# I2C_Lego_PowerFunctions_Board_v1_0B.net
KiCad netlist of a schematic drawn in EAGLE
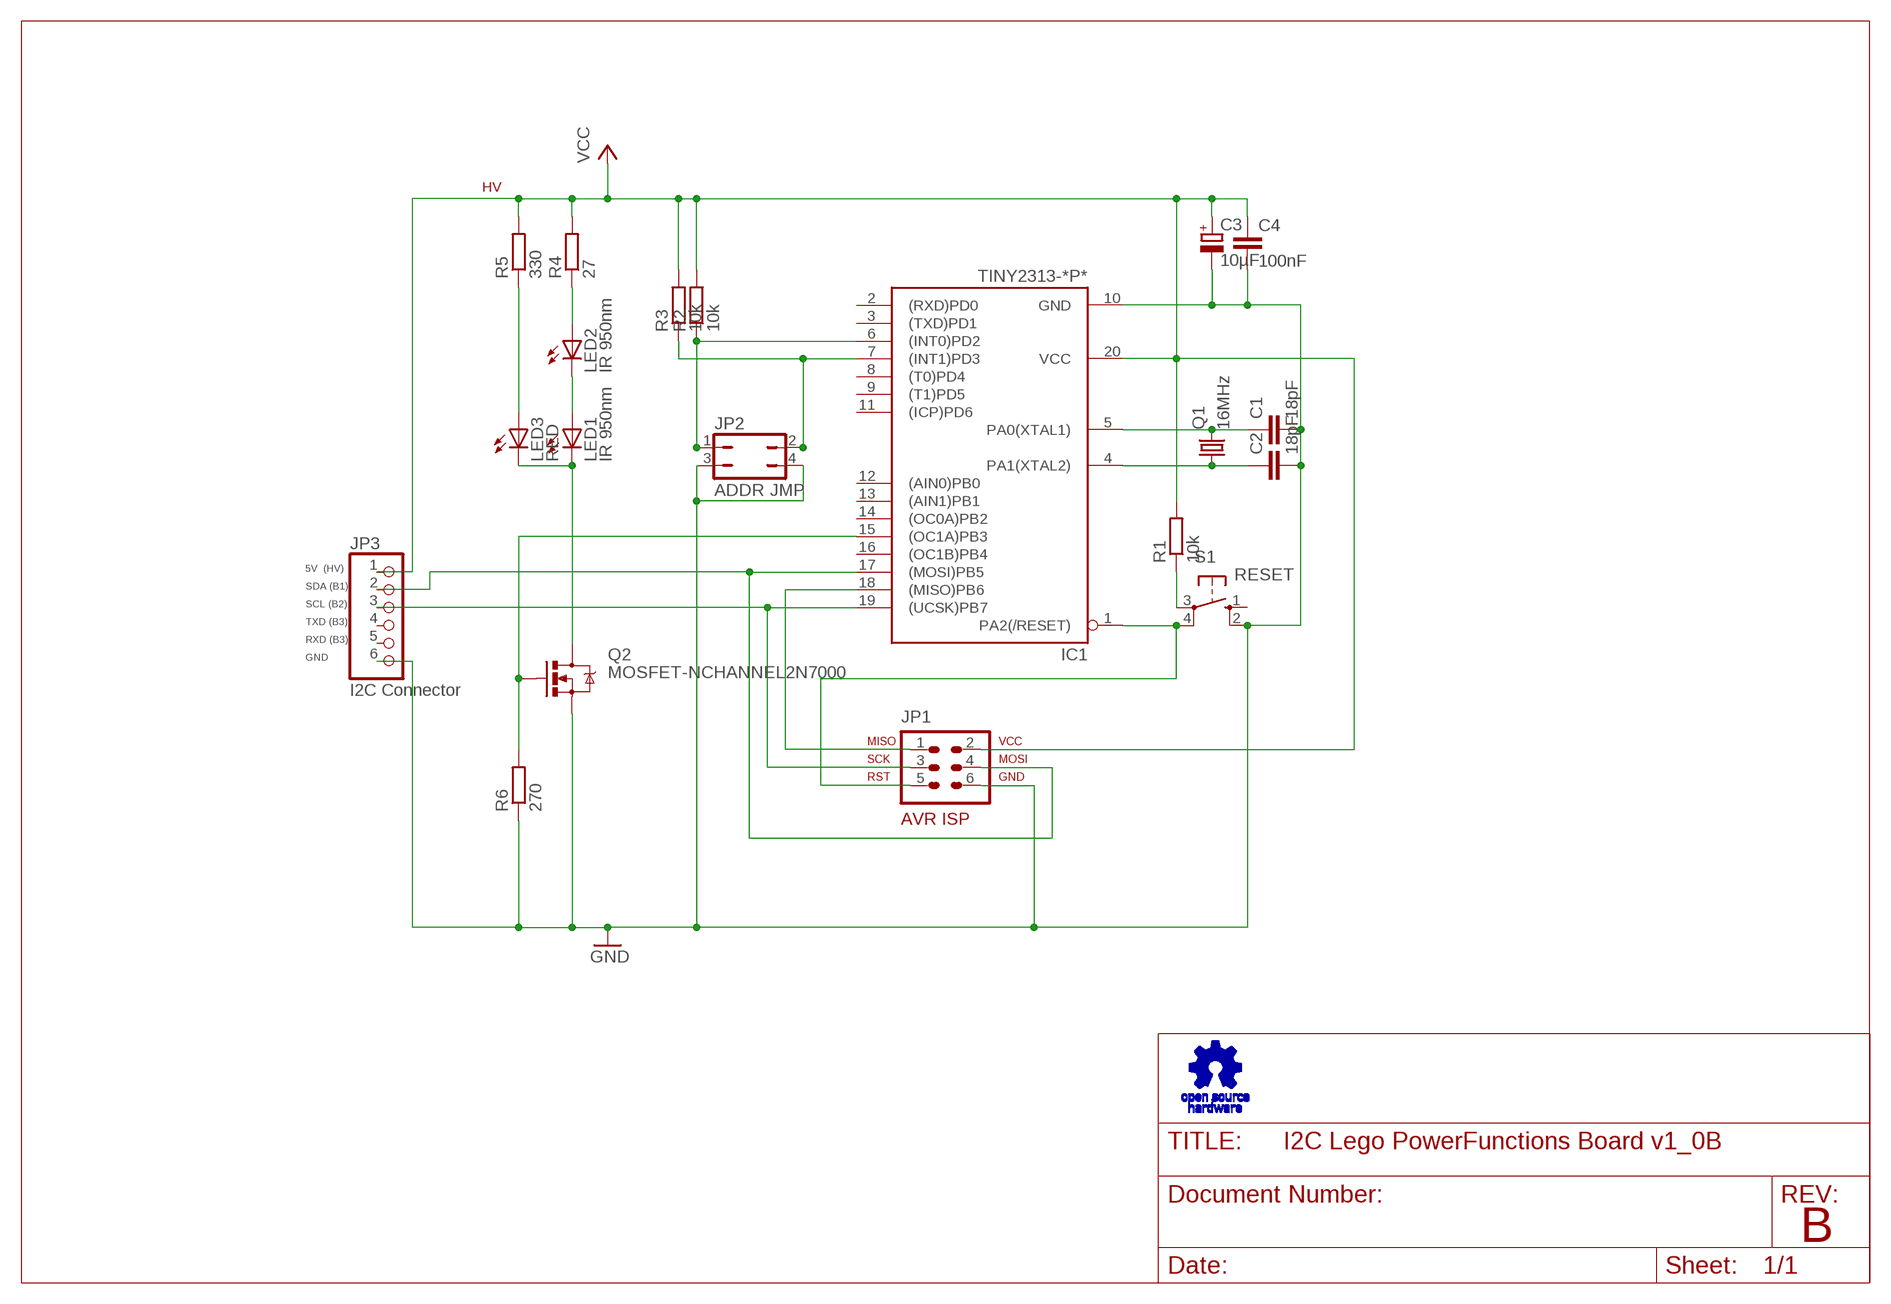
[diagram p0: schematic, sheet 1]

(export (version "E")
  (design (tool "Eeschema 10.0.6"))
  (components
    (comp (ref "C1")
      (value "18pF")
      (footprint "eagle-import:C025-025X050")
      (libsource (lib "eagle-import") (part "C-EU025-025X050"))
    )
    (comp (ref "C2")
      (value "18pF")
      (footprint "eagle-import:C025-025X050")
      (libsource (lib "eagle-import") (part "C-EU025-025X050"))
    )
    (comp (ref "C3")
      (value "10µF")
      (footprint "eagle-import:E2,5-6")
      (libsource (lib "eagle-import") (part "CPOL-EUE2.5-6"))
    )
    (comp (ref "C4")
      (value "100nF")
      (footprint "eagle-import:C050-030X075")
      (libsource (lib "eagle-import") (part "C-EU050-030X075"))
    )
    (comp (ref "IC1")
      (value "TINY2313-*P*")
      (footprint "eagle-import:DIL20")
      (libsource (lib "eagle-import") (part "TINY2313-P"))
    )
    (comp (ref "JP1")
      (value "AVR-ISP-6VERT")
      (footprint "eagle-import:AVR-ISP-6")
      (libsource (lib "eagle-import") (part "AVR-ISP-6VERT"))
    )
    (comp (ref "JP2")
      (value "ADDR JMP")
      (footprint "eagle-import:JP2Q")
      (libsource (lib "eagle-import") (part "JP2Q"))
    )
    (comp (ref "JP3")
      (value "I2C Connector")
      (footprint "eagle-import:1X06")
      (libsource (lib "eagle-import") (part "PINHD-1X6"))
    )
    (comp (ref "LED1")
      (value "IR 950nm")
      (footprint "eagle-import:LED5MM")
      (libsource (lib "eagle-import") (part "LED5MM"))
    )
    (comp (ref "LED2")
      (value "IR 950nm")
      (footprint "eagle-import:LED5MM")
      (libsource (lib "eagle-import") (part "LED5MM"))
    )
    (comp (ref "LED3")
      (value "RED")
      (footprint "eagle-import:LED3MM")
      (libsource (lib "eagle-import") (part "LED3MM"))
    )
    (comp (ref "Q1")
      (value "16MHz")
      (footprint "eagle-import:HC49_S")
      (libsource (lib "eagle-import") (part "CRYSTALHC49S"))
    )
    (comp (ref "Q2")
      (value "MOSFET-NCHANNEL2N7000")
      (footprint "eagle-import:TO-92")
      (libsource (lib "eagle-import") (part "MOSFET-NCHANNEL2N7000"))
    )
    (comp (ref "R1")
      (value "10k")
      (footprint "eagle-import:0207_10")
      (libsource (lib "eagle-import") (part "R-EU_0207_10"))
    )
    (comp (ref "R2")
      (value "10k")
      (footprint "eagle-import:0207_10")
      (libsource (lib "eagle-import") (part "R-EU_0207_10"))
    )
    (comp (ref "R3")
      (value "10k")
      (footprint "eagle-import:0207_10")
      (libsource (lib "eagle-import") (part "R-EU_0207_10"))
    )
    (comp (ref "R4")
      (value "27")
      (footprint "eagle-import:0207_10")
      (libsource (lib "eagle-import") (part "R-EU_0207_10"))
    )
    (comp (ref "R5")
      (value "330")
      (footprint "eagle-import:0207_10")
      (libsource (lib "eagle-import") (part "R-EU_0207_10"))
    )
    (comp (ref "R6")
      (value "270")
      (footprint "eagle-import:0207_10")
      (libsource (lib "eagle-import") (part "R-EU_0207_10"))
    )
    (comp (ref "S1")
      (value "RESET")
      (footprint "eagle-import:B3F-10XX")
      (fields (field (name "MPN") "B3F-1000"))
      (libsource (lib "eagle-import") (part "10-XX"))
    )
  )
  (nets
    (net (code "1") (name "GND") (class "Default")
      (node (ref "C1") (pin "2") (pinfunction "2_2") (pintype "passive"))
      (node (ref "C2") (pin "2") (pinfunction "2_2") (pintype "passive"))
      (node (ref "C3") (pin "-") (pinfunction "-_-") (pintype "passive"))
      (node (ref "C4") (pin "2") (pinfunction "2_2") (pintype "passive"))
      (node (ref "IC1") (pin "10") (pinfunction "GND_10") (pintype "power_in"))
      (node (ref "JP1") (pin "6") (pinfunction "6_6") (pintype "passive"))
      (node (ref "JP2") (pin "3") (pinfunction "3_3") (pintype "passive"))
      (node (ref "JP2") (pin "4") (pinfunction "4_4") (pintype "passive"))
      (node (ref "JP3") (pin "6") (pinfunction "6_6") (pintype "passive"))
      (node (ref "Q2") (pin "1") (pinfunction "S_1") (pintype "passive"))
      (node (ref "R6") (pin "1") (pinfunction "1_1") (pintype "passive"))
      (node (ref "S1") (pin "2") (pinfunction "S1_2") (pintype "passive"))
    )
    (net (code "2") (name "Net-(IC1-(INT0)PD2)") (class "Default")
      (node (ref "IC1") (pin "6") (pinfunction "(INT0)PD2_6") (pintype "bidirectional"))
      (node (ref "JP2") (pin "1") (pinfunction "1_1") (pintype "passive"))
      (node (ref "R2") (pin "1") (pinfunction "1_1") (pintype "passive"))
    )
    (net (code "3") (name "Net-(IC1-(INT1)PD3)") (class "Default")
      (node (ref "IC1") (pin "7") (pinfunction "(INT1)PD3_7") (pintype "bidirectional"))
      (node (ref "JP2") (pin "2") (pinfunction "2_2") (pintype "passive"))
      (node (ref "R3") (pin "1") (pinfunction "1_1") (pintype "passive"))
    )
    (net (code "4") (name "Net-(IC1-(MISO)PB6)") (class "Default")
      (node (ref "IC1") (pin "18") (pinfunction "(MISO)PB6_18") (pintype "bidirectional"))
      (node (ref "JP1") (pin "1") (pinfunction "1_1") (pintype "passive"))
    )
    (net (code "5") (name "Net-(IC1-(MOSI)PB5)") (class "Default")
      (node (ref "IC1") (pin "17") (pinfunction "(MOSI)PB5_17") (pintype "bidirectional"))
      (node (ref "JP1") (pin "4") (pinfunction "4_4") (pintype "passive"))
      (node (ref "JP3") (pin "2") (pinfunction "2_2") (pintype "passive"))
    )
    (net (code "6") (name "Net-(IC1-(OC1A)PB3)") (class "Default")
      (node (ref "IC1") (pin "15") (pinfunction "(OC1A)PB3_15") (pintype "bidirectional"))
      (node (ref "Q2") (pin "2") (pinfunction "G_2") (pintype "passive"))
      (node (ref "R6") (pin "2") (pinfunction "2_2") (pintype "passive"))
    )
    (net (code "7") (name "Net-(IC1-(UCSK)PB7)") (class "Default")
      (node (ref "IC1") (pin "19") (pinfunction "(UCSK)PB7_19") (pintype "bidirectional"))
      (node (ref "JP1") (pin "3") (pinfunction "3_3") (pintype "passive"))
      (node (ref "JP3") (pin "3") (pinfunction "3_3") (pintype "passive"))
    )
    (net (code "8") (name "Net-(IC1-PA0(XTAL1))") (class "Default")
      (node (ref "C1") (pin "1") (pinfunction "1_1") (pintype "passive"))
      (node (ref "IC1") (pin "5") (pinfunction "PA0(XTAL1)_5") (pintype "bidirectional"))
      (node (ref "Q1") (pin "2") (pinfunction "2_2") (pintype "passive"))
    )
    (net (code "9") (name "Net-(IC1-PA1(XTAL2))") (class "Default")
      (node (ref "C2") (pin "1") (pinfunction "1_1") (pintype "passive"))
      (node (ref "IC1") (pin "4") (pinfunction "PA1(XTAL2)_4") (pintype "bidirectional"))
      (node (ref "Q1") (pin "1") (pinfunction "1_1") (pintype "passive"))
    )
    (net (code "10") (name "Net-(IC1-PA2({slash}RESET))") (class "Default")
      (node (ref "IC1") (pin "1") (pinfunction "PA2(/RESET)_1") (pintype "input"))
      (node (ref "JP1") (pin "5") (pinfunction "5_5") (pintype "passive"))
      (node (ref "S1") (pin "4") (pinfunction "P1_4") (pintype "passive"))
    )
    (net (code "11") (name "Net-(LED1-C)") (class "Default")
      (node (ref "LED1") (pin "K") (pinfunction "C_K") (pintype "passive"))
      (node (ref "LED3") (pin "K") (pinfunction "C_K") (pintype "passive"))
      (node (ref "Q2") (pin "3") (pinfunction "D_3") (pintype "passive"))
    )
    (net (code "12") (name "Net-(LED2-C)") (class "Default")
      (node (ref "LED1") (pin "A") (pinfunction "A_A") (pintype "passive"))
      (node (ref "LED2") (pin "K") (pinfunction "C_K") (pintype "passive"))
    )
    (net (code "13") (name "Net-(LED2-PadA)") (class "Default")
      (node (ref "LED2") (pin "A") (pinfunction "A_A") (pintype "passive"))
      (node (ref "R4") (pin "1") (pinfunction "1_1") (pintype "passive"))
    )
    (net (code "14") (name "Net-(LED3-PadA)") (class "Default")
      (node (ref "LED3") (pin "A") (pinfunction "A_A") (pintype "passive"))
      (node (ref "R5") (pin "1") (pinfunction "1_1") (pintype "passive"))
    )
    (net (code "15") (name "Net-(S1-P)") (class "Default")
      (node (ref "R1") (pin "1") (pinfunction "1_1") (pintype "passive"))
      (node (ref "S1") (pin "3") (pinfunction "P_3") (pintype "passive"))
    )
    (net (code "16") (name "VCC") (class "Default")
      (node (ref "C3") (pin "+") (pinfunction "+_+") (pintype "passive"))
      (node (ref "C4") (pin "1") (pinfunction "1_1") (pintype "passive"))
      (node (ref "IC1") (pin "20") (pinfunction "VCC_20") (pintype "power_in"))
      (node (ref "JP1") (pin "2") (pinfunction "2_2") (pintype "passive"))
      (node (ref "JP3") (pin "1") (pinfunction "1_1") (pintype "passive"))
      (node (ref "R1") (pin "2") (pinfunction "2_2") (pintype "passive"))
      (node (ref "R2") (pin "2") (pinfunction "2_2") (pintype "passive"))
      (node (ref "R3") (pin "2") (pinfunction "2_2") (pintype "passive"))
      (node (ref "R4") (pin "2") (pinfunction "2_2") (pintype "passive"))
      (node (ref "R5") (pin "2") (pinfunction "2_2") (pintype "passive"))
    )
    (net (code "17") (name "unconnected-(IC1-(AIN0)PB0-Pad12)") (class "Default")
      (node (ref "IC1") (pin "12") (pinfunction "(AIN0)PB0_12") (pintype "bidirectional"))
    )
    (net (code "18") (name "unconnected-(IC1-(AIN1)PB1-Pad13)") (class "Default")
      (node (ref "IC1") (pin "13") (pinfunction "(AIN1)PB1_13") (pintype "bidirectional"))
    )
    (net (code "19") (name "unconnected-(IC1-(ICP)PD6-Pad11)") (class "Default")
      (node (ref "IC1") (pin "11") (pinfunction "(ICP)PD6_11") (pintype "bidirectional"))
    )
    (net (code "20") (name "unconnected-(IC1-(OC0A)PB2-Pad14)") (class "Default")
      (node (ref "IC1") (pin "14") (pinfunction "(OC0A)PB2_14") (pintype "bidirectional"))
    )
    (net (code "21") (name "unconnected-(IC1-(OC1B)PB4-Pad16)") (class "Default")
      (node (ref "IC1") (pin "16") (pinfunction "(OC1B)PB4_16") (pintype "bidirectional"))
    )
    (net (code "22") (name "unconnected-(IC1-(RXD)PD0-Pad2)") (class "Default")
      (node (ref "IC1") (pin "2") (pinfunction "(RXD)PD0_2") (pintype "bidirectional"))
    )
    (net (code "23") (name "unconnected-(IC1-(T0)PD4-Pad8)") (class "Default")
      (node (ref "IC1") (pin "8") (pinfunction "(T0)PD4_8") (pintype "bidirectional"))
    )
    (net (code "24") (name "unconnected-(IC1-(T1)PD5-Pad9)") (class "Default")
      (node (ref "IC1") (pin "9") (pinfunction "(T1)PD5_9") (pintype "bidirectional"))
    )
    (net (code "25") (name "unconnected-(IC1-(TXD)PD1-Pad3)") (class "Default")
      (node (ref "IC1") (pin "3") (pinfunction "(TXD)PD1_3") (pintype "bidirectional"))
    )
    (net (code "26") (name "unconnected-(JP3-Pad4)") (class "Default")
      (node (ref "JP3") (pin "4") (pinfunction "4_4") (pintype "passive"))
    )
    (net (code "27") (name "unconnected-(JP3-Pad5)") (class "Default")
      (node (ref "JP3") (pin "5") (pinfunction "5_5") (pintype "passive"))
    )
    (net (code "28") (name "unconnected-(S1-S-Pad1)") (class "Default")
      (node (ref "S1") (pin "1") (pinfunction "S_1") (pintype "passive"))
    )
  )
)
